# Total.net
KiCad netlist of a schematic drawn in Altium Designer
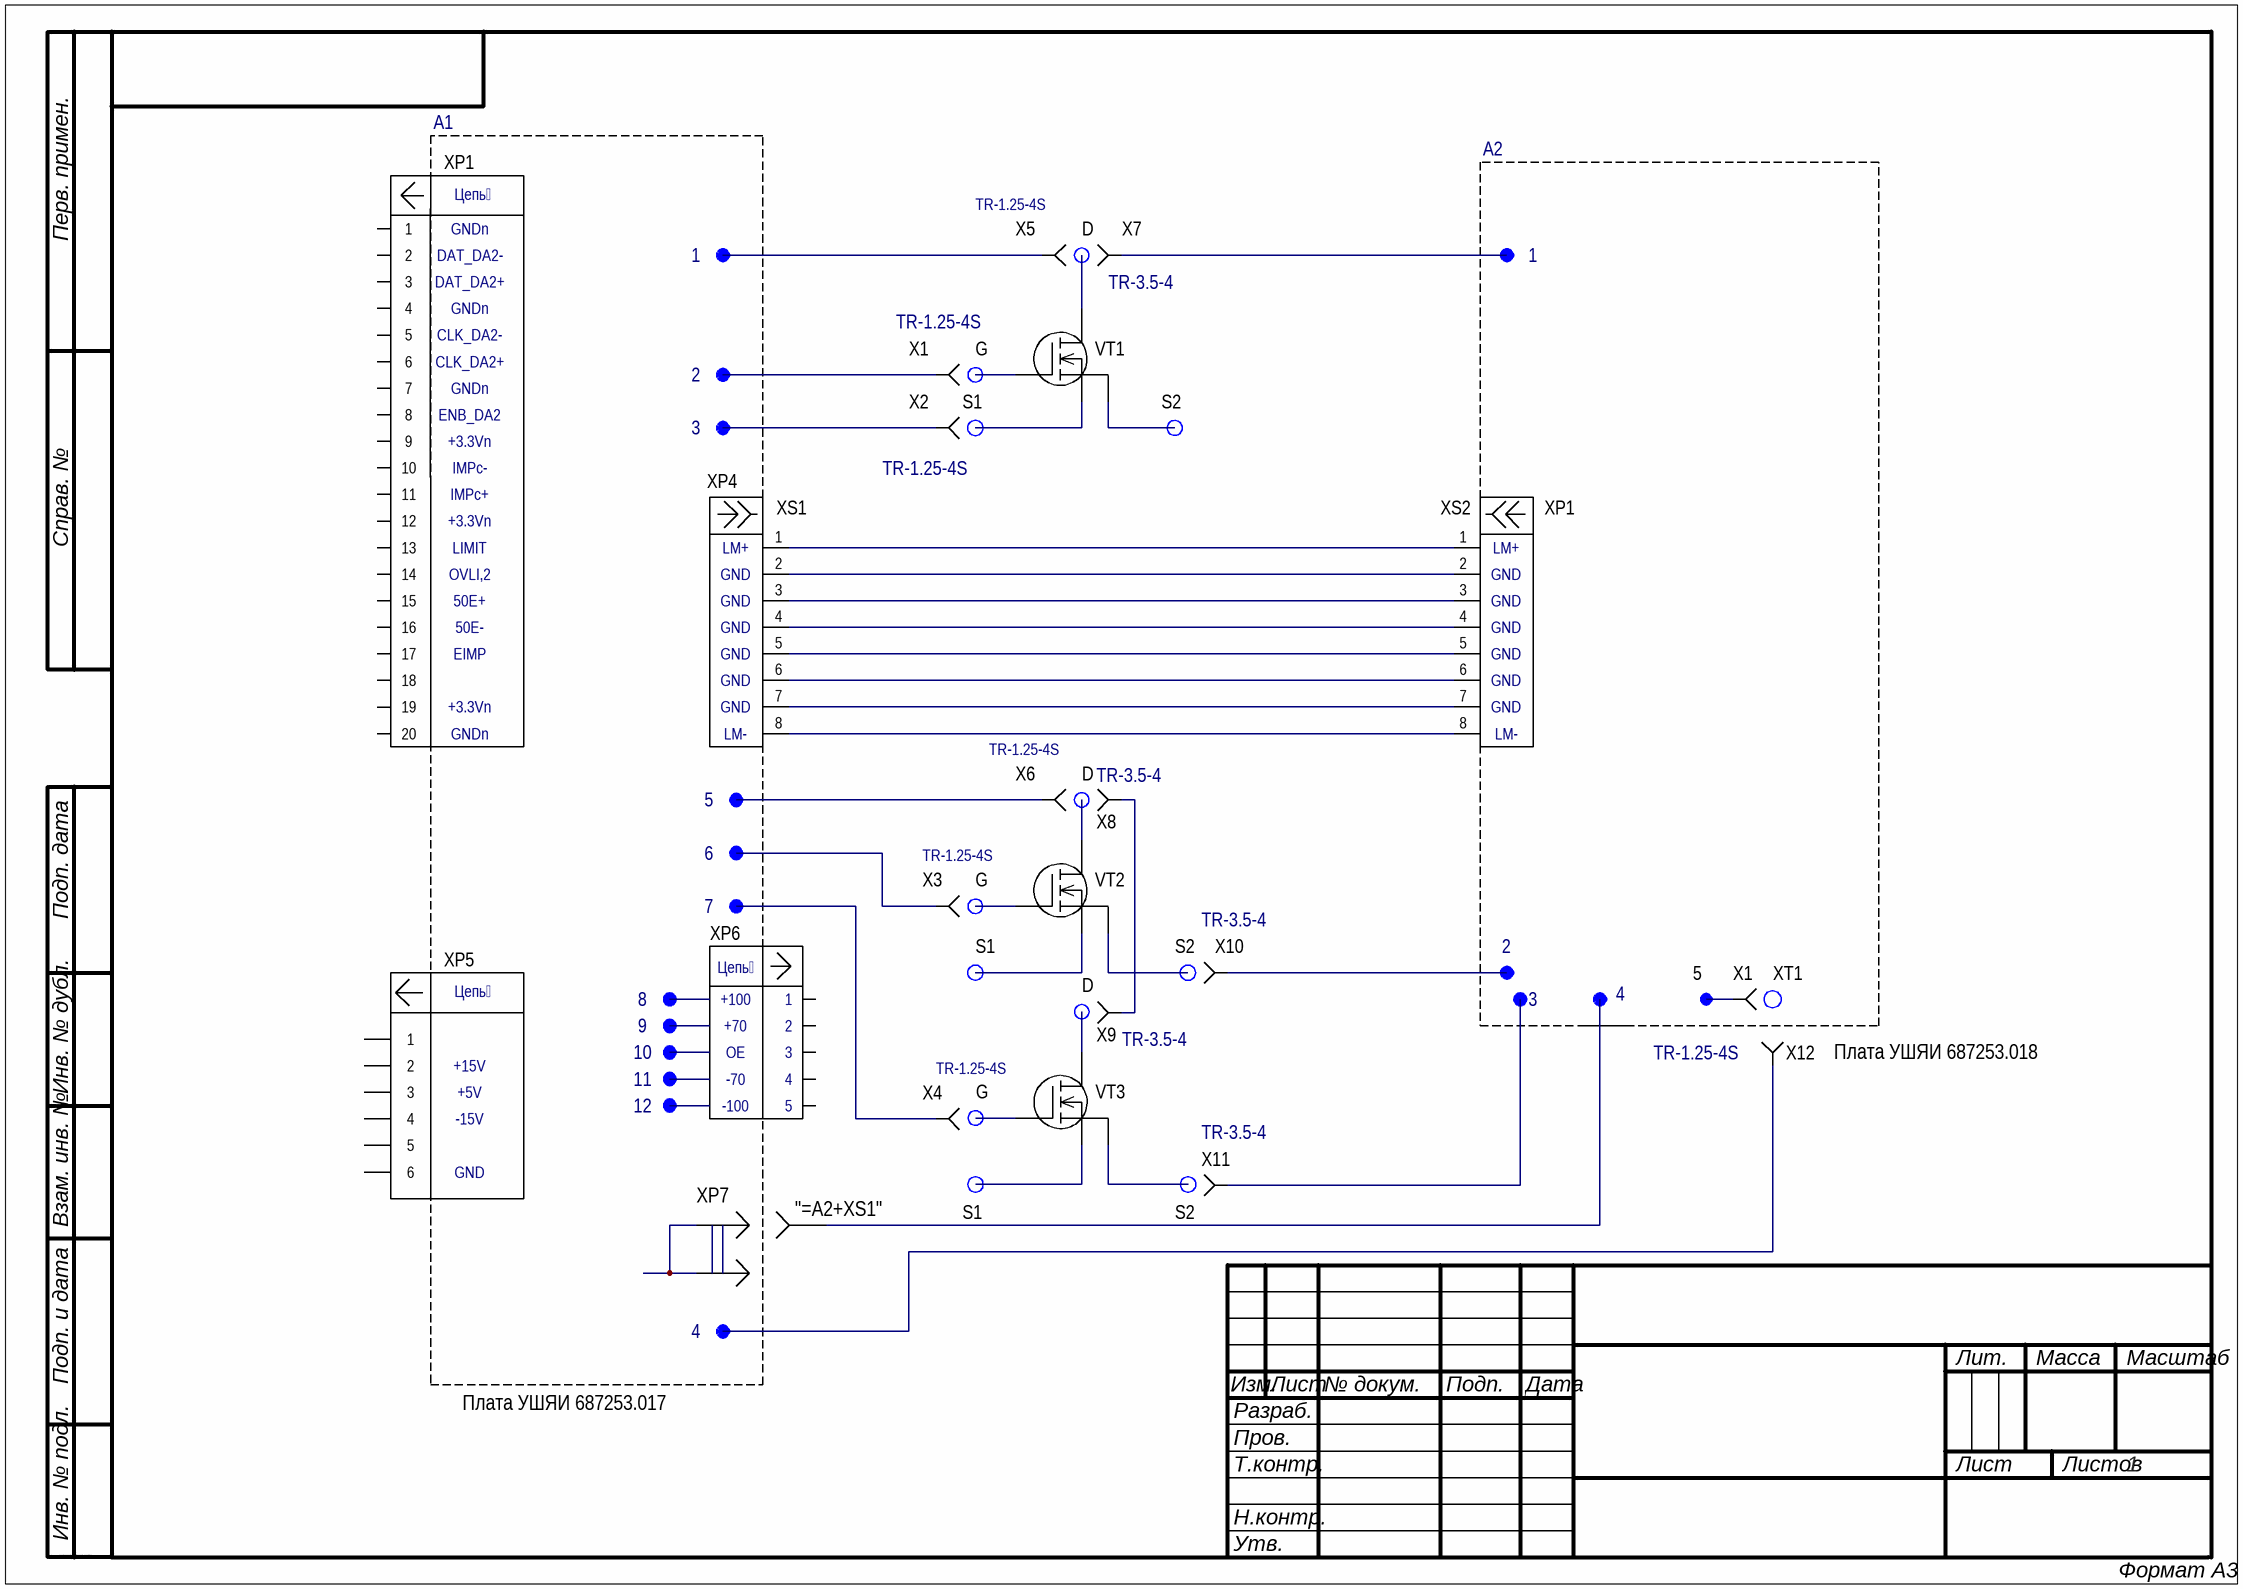
[diagram p0: Total.SchDoc]

(export (version "E")
  (design (tool "Eeschema 10.0.6"))
  (components
    (comp (ref "5") (value "OTV") (libsource (lib "МНИПИ_Остальное") (part "OTV")))
    (comp (ref "VT1")
      (value "пе")
      (footprint "SOT-227B")
      (libsource (lib "МНИПИ_Транзисторы") (part "IXFN210N30P3"))
    )
    (comp (ref "VT2")
      (value "IXFN210N30P3")
      (footprint "SOT-227B")
      (libsource (lib "МНИПИ_Транзисторы") (part "IXFN210N30P3"))
    )
    (comp (ref "VT3")
      (value "IXFN210N30P3")
      (footprint "SOT-227B")
      (libsource (lib "МНИПИ_Транзисторы") (part "IXFN210N30P3"))
    )
    (comp (ref "X2") (value "TR-1.25-4S") (libsource (lib "МНИПИ_Разъемы") (part "TR-1.25-4S")))
    (comp (ref "X3") (value "TR-1.25-4S") (libsource (lib "МНИПИ_Разъемы") (part "TR-1.25-4S")))
    (comp (ref "X4") (value "TR-1.25-4S") (libsource (lib "МНИПИ_Разъемы") (part "TR-1.25-4S")))
    (comp (ref "X5") (value "TR-1.25-4S") (libsource (lib "МНИПИ_Разъемы") (part "TR-1.25-4S")))
    (comp (ref "X6") (value "TR-1.25-4S") (libsource (lib "МНИПИ_Разъемы") (part "TR-1.25-4S")))
    (comp (ref "X7")
      (value "TR-3.5-4")
      (description "TR-3.5-4 клемма типа \"O\"")
      (libsource (lib "МНИПИ_Разъемы") (part "TR-3.5-4"))
    )
    (comp (ref "X8")
      (value "TR-3.5-4")
      (description "TR-3.5-4 клемма типа \"O\"")
      (libsource (lib "МНИПИ_Разъемы") (part "TR-3.5-4"))
    )
    (comp (ref "X9")
      (value "TR-3.5-4")
      (description "TR-3.5-4 клемма типа \"O\"")
      (libsource (lib "МНИПИ_Разъемы") (part "TR-3.5-4"))
    )
    (comp (ref "X10")
      (value "TR-3.5-4")
      (description "TR-3.5-4 клемма типа \"O\"")
      (libsource (lib "МНИПИ_Разъемы") (part "TR-3.5-4"))
    )
    (comp (ref "X11")
      (value "TR-3.5-4")
      (description "TR-3.5-4 клемма типа \"O\"")
      (libsource (lib "МНИПИ_Разъемы") (part "TR-3.5-4"))
    )
    (comp (ref "X12") (value "TR-1.25-4S") (libsource (lib "МНИПИ_Разъемы") (part "TR-1.25-4S")))
    (comp (ref "XP1")
      (value "BH2-20")
      (description "IDC2-20MS DS1014 20 pin")
      (libsource (lib "МНИПИ_Разъемы") (part "BH2-20"))
    )
    (comp (ref "XP5")
      (value "280372-2")
      (footprint "МНИПИ_Разъемы:280372-2")
      (description "Connector")
      (libsource (lib "МНИПИ_Разъемы") (part "280372-2"))
    )
    (comp (ref "XP6") (value "MNL-350810-1") (libsource (lib "МНИПИ_Разъемы") (part "MNL-350810-1")))
    (comp (ref "XS1") (value "280361") (libsource (lib "МНИПИ_Разъемы") (part "280361")))
    (comp (ref "XS2") (value "280361") (libsource (lib "МНИПИ_Разъемы") (part "280361")))
    (comp (ref "XT1") (value "УШЯИ.685631.123") (libsource (lib "МНИПИ_Остальное") (part "УШЯИ.685631.123")))
  )
  (nets
    (net (code "1") (name "Net-(XS1-Pad1)") (class "Default")
      (node (ref "XS1") (pin "1") (pinfunction "1_1") (pintype "passive"))
      (node (ref "XS2") (pin "1") (pinfunction "1_1") (pintype "passive"))
    )
    (net (code "2") (name "Net-(XS1-Pad2)") (class "Default")
      (node (ref "XS1") (pin "2") (pinfunction "2_2") (pintype "passive"))
      (node (ref "XS2") (pin "2") (pinfunction "2_2") (pintype "passive"))
    )
    (net (code "3") (name "Net-(XS1-Pad3)") (class "Default")
      (node (ref "XS1") (pin "3") (pinfunction "3_3") (pintype "passive"))
      (node (ref "XS2") (pin "3") (pinfunction "3_3") (pintype "passive"))
    )
    (net (code "4") (name "Net-(XS1-Pad4)") (class "Default")
      (node (ref "XS1") (pin "4") (pinfunction "4_4") (pintype "passive"))
      (node (ref "XS2") (pin "4") (pinfunction "4_4") (pintype "passive"))
    )
    (net (code "5") (name "Net-(XS1-Pad5)") (class "Default")
      (node (ref "XS1") (pin "5") (pinfunction "5_5") (pintype "passive"))
      (node (ref "XS2") (pin "5") (pinfunction "5_5") (pintype "passive"))
    )
    (net (code "6") (name "Net-(XS1-Pad6)") (class "Default")
      (node (ref "XS1") (pin "6") (pinfunction "6_6") (pintype "passive"))
      (node (ref "XS2") (pin "6") (pinfunction "6_6") (pintype "passive"))
    )
    (net (code "7") (name "Net-(XS1-Pad7)") (class "Default")
      (node (ref "XS1") (pin "7") (pinfunction "7_7") (pintype "passive"))
      (node (ref "XS2") (pin "7") (pinfunction "7_7") (pintype "passive"))
    )
    (net (code "8") (name "Net-(XS1-Pad8)") (class "Default")
      (node (ref "XS1") (pin "8") (pinfunction "8_8") (pintype "passive"))
      (node (ref "XS2") (pin "8") (pinfunction "8_8") (pintype "passive"))
    )
    (net (code "9") (name "unconnected-(5-Pad)") (class "Default")
      (node (ref "5") (pin "") (pintype "passive"))
    )
    (net (code "10") (name "unconnected-(VT1-PadD)") (class "Default")
      (node (ref "VT1") (pin "D") (pinfunction "D_D") (pintype "passive"))
    )
    (net (code "11") (name "unconnected-(VT1-PadG)") (class "Default")
      (node (ref "VT1") (pin "G") (pinfunction "G_G") (pintype "passive"))
    )
    (net (code "12") (name "unconnected-(VT1-PadS)") (class "Default")
      (node (ref "VT1") (pin "S") (pinfunction "S_S") (pintype "passive"))
    )
    (net (code "13") (name "unconnected-(VT1-PadS)_1") (class "Default")
      (node (ref "VT1") (pin "S") (pinfunction "S_S") (pintype "passive"))
    )
    (net (code "14") (name "unconnected-(VT2-PadD)") (class "Default")
      (node (ref "VT2") (pin "D") (pinfunction "D_D") (pintype "passive"))
    )
    (net (code "15") (name "unconnected-(VT2-PadG)") (class "Default")
      (node (ref "VT2") (pin "G") (pinfunction "G_G") (pintype "passive"))
    )
    (net (code "16") (name "unconnected-(VT2-PadS)") (class "Default")
      (node (ref "VT2") (pin "S") (pinfunction "S_S") (pintype "passive"))
    )
    (net (code "17") (name "unconnected-(VT2-PadS)_1") (class "Default")
      (node (ref "VT2") (pin "S") (pinfunction "S_S") (pintype "passive"))
    )
    (net (code "18") (name "unconnected-(VT3-PadD)") (class "Default")
      (node (ref "VT3") (pin "D") (pinfunction "D_D") (pintype "passive"))
    )
    (net (code "19") (name "unconnected-(VT3-PadG)") (class "Default")
      (node (ref "VT3") (pin "G") (pinfunction "G_G") (pintype "passive"))
    )
    (net (code "20") (name "unconnected-(VT3-PadS)") (class "Default")
      (node (ref "VT3") (pin "S") (pinfunction "S_S") (pintype "passive"))
    )
    (net (code "21") (name "unconnected-(VT3-PadS)_1") (class "Default")
      (node (ref "VT3") (pin "S") (pinfunction "S_S") (pintype "passive"))
    )
    (net (code "22") (name "unconnected-(XP1-Pad1)") (class "Default")
      (node (ref "XP1") (pin "1") (pinfunction "1_1") (pintype "passive"))
    )
    (net (code "23") (name "unconnected-(XP1-Pad2)") (class "Default")
      (node (ref "XP1") (pin "2") (pinfunction "2_2") (pintype "passive"))
    )
    (net (code "24") (name "unconnected-(XP1-Pad3)") (class "Default")
      (node (ref "XP1") (pin "3") (pinfunction "3_3") (pintype "passive"))
    )
    (net (code "25") (name "unconnected-(XP1-Pad4)") (class "Default")
      (node (ref "XP1") (pin "4") (pinfunction "4_4") (pintype "passive"))
    )
    (net (code "26") (name "unconnected-(XP1-Pad5)") (class "Default")
      (node (ref "XP1") (pin "5") (pinfunction "5_5") (pintype "passive"))
    )
    (net (code "27") (name "unconnected-(XP1-Pad6)") (class "Default")
      (node (ref "XP1") (pin "6") (pinfunction "6_6") (pintype "passive"))
    )
    (net (code "28") (name "unconnected-(XP1-Pad7)") (class "Default")
      (node (ref "XP1") (pin "7") (pinfunction "7_7") (pintype "passive"))
    )
    (net (code "29") (name "unconnected-(XP1-Pad8)") (class "Default")
      (node (ref "XP1") (pin "8") (pinfunction "8_8") (pintype "passive"))
    )
    (net (code "30") (name "unconnected-(XP1-Pad9)") (class "Default")
      (node (ref "XP1") (pin "9") (pinfunction "9_9") (pintype "passive"))
    )
    (net (code "31") (name "unconnected-(XP1-Pad10)") (class "Default")
      (node (ref "XP1") (pin "10") (pinfunction "10_10") (pintype "passive"))
    )
    (net (code "32") (name "unconnected-(XP1-Pad11)") (class "Default")
      (node (ref "XP1") (pin "11") (pinfunction "11_11") (pintype "passive"))
    )
    (net (code "33") (name "unconnected-(XP1-Pad12)") (class "Default")
      (node (ref "XP1") (pin "12") (pinfunction "12_12") (pintype "passive"))
    )
    (net (code "34") (name "unconnected-(XP1-Pad13)") (class "Default")
      (node (ref "XP1") (pin "13") (pinfunction "13_13") (pintype "passive"))
    )
    (net (code "35") (name "unconnected-(XP1-Pad14)") (class "Default")
      (node (ref "XP1") (pin "14") (pinfunction "14_14") (pintype "passive"))
    )
    (net (code "36") (name "unconnected-(XP1-Pad15)") (class "Default")
      (node (ref "XP1") (pin "15") (pinfunction "15_15") (pintype "passive"))
    )
    (net (code "37") (name "unconnected-(XP1-Pad16)") (class "Default")
      (node (ref "XP1") (pin "16") (pinfunction "16_16") (pintype "passive"))
    )
    (net (code "38") (name "unconnected-(XP1-Pad17)") (class "Default")
      (node (ref "XP1") (pin "17") (pinfunction "17_17") (pintype "passive"))
    )
    (net (code "39") (name "unconnected-(XP1-Pad18)") (class "Default")
      (node (ref "XP1") (pin "18") (pinfunction "18_18") (pintype "passive"))
    )
    (net (code "40") (name "unconnected-(XP1-Pad19)") (class "Default")
      (node (ref "XP1") (pin "19") (pinfunction "19_19") (pintype "passive"))
    )
    (net (code "41") (name "unconnected-(XP1-Pad20)") (class "Default")
      (node (ref "XP1") (pin "20") (pinfunction "20_20") (pintype "passive"))
    )
    (net (code "42") (name "unconnected-(XP5-Pad1)") (class "Default")
      (node (ref "XP5") (pin "1") (pinfunction "1_1") (pintype "passive"))
    )
    (net (code "43") (name "unconnected-(XP5-Pad2)") (class "Default")
      (node (ref "XP5") (pin "2") (pinfunction "2_2") (pintype "passive"))
    )
    (net (code "44") (name "unconnected-(XP5-Pad3)") (class "Default")
      (node (ref "XP5") (pin "3") (pinfunction "3_3") (pintype "passive"))
    )
    (net (code "45") (name "unconnected-(XP5-Pad4)") (class "Default")
      (node (ref "XP5") (pin "4") (pinfunction "4_4") (pintype "passive"))
    )
    (net (code "46") (name "unconnected-(XP5-Pad5)") (class "Default")
      (node (ref "XP5") (pin "5") (pinfunction "5_5") (pintype "passive"))
    )
    (net (code "47") (name "unconnected-(XP5-Pad6)") (class "Default")
      (node (ref "XP5") (pin "6") (pinfunction "6_6") (pintype "passive"))
    )
    (net (code "48") (name "unconnected-(XP6-Pad1)") (class "Default")
      (node (ref "XP6") (pin "1") (pinfunction "1_1") (pintype "passive"))
    )
    (net (code "49") (name "unconnected-(XP6-Pad2)") (class "Default")
      (node (ref "XP6") (pin "2") (pinfunction "2_2") (pintype "passive"))
    )
    (net (code "50") (name "unconnected-(XP6-Pad3)") (class "Default")
      (node (ref "XP6") (pin "3") (pinfunction "3_3") (pintype "passive"))
    )
    (net (code "51") (name "unconnected-(XP6-Pad4)") (class "Default")
      (node (ref "XP6") (pin "4") (pinfunction "4_4") (pintype "passive"))
    )
    (net (code "52") (name "unconnected-(XP6-Pad5)") (class "Default")
      (node (ref "XP6") (pin "5") (pinfunction "5_5") (pintype "passive"))
    )
  )
)
